# Morpheus_MEM.net
KiCad netlist of a schematic drawn in Altium Designer
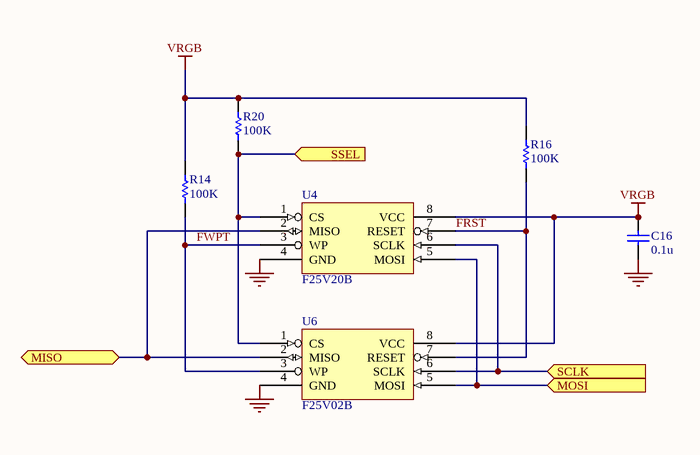
[diagram p0: Morpheus_MEM.SchDoc]

(export (version "E")
  (design (tool "Eeschema 10.0.6"))
  (components
    (comp (ref "C16")
      (value "0.1u")
      (footprint "CAP0402")
      (description "Chip capacitor")
      (fields (field (name "TOLERANCE") "10%") (field (name "VOLTAGE") "50V"))
      (libsource (lib "Hello") (part "C_0.1u_10_50_X7R_0402"))
    )
    (comp (ref "R14")
      (value "100K")
      (footprint "RES0402")
      (description "Chip Resistor")
      (fields (field (name "TOLERANCE") "5 %") (field (name "POWER") "0.1 W"))
      (libsource (lib "Hello") (part "R_100K_5_0.1_0402"))
    )
    (comp (ref "R16")
      (value "100K")
      (footprint "RES0402")
      (description "Chip Resistor")
      (fields (field (name "TOLERANCE") "5 %") (field (name "POWER") "0.1 W"))
      (libsource (lib "Hello") (part "R_100K_5_0.1_0402"))
    )
    (comp (ref "R20")
      (value "100K")
      (footprint "RES0402")
      (description "Chip Resistor")
      (fields (field (name "TOLERANCE") "5 %") (field (name "POWER") "0.1 W"))
      (libsource (lib "Hello") (part "R_100K_5_0.1_0402"))
    )
    (comp (ref "U4")
      (value "F25V20B")
      (footprint "DFN127P600x500x80-8N")
      (description "Cypress SPI FRAM 256Kx8")
      (libsource (lib "dykes") (part "FM25V20B"))
    )
    (comp (ref "U6")
      (value "F25V02B")
      (footprint "DFN95P5000x4500x80-8N")
      (description "Cypress SPI FRAM 32Kx8")
      (libsource (lib "dykes") (part "FM25V02B"))
    )
  )
  (nets
    (net (code "1") (name "/FRST") (class "Default")
      (node (ref "R16") (pin "1") (pinfunction "1_1") (pintype "passive"))
      (node (ref "U4") (pin "7") (pinfunction "RESET_7") (pintype "input"))
      (node (ref "U6") (pin "7") (pinfunction "RESET_7") (pintype "input"))
    )
    (net (code "2") (name "/FWPT") (class "Default")
      (node (ref "R14") (pin "1") (pinfunction "1_1") (pintype "passive"))
      (node (ref "U4") (pin "3") (pinfunction "WP_3") (pintype "passive"))
      (node (ref "U6") (pin "3") (pinfunction "WP_3") (pintype "passive"))
    )
    (net (code "3") (name "/MISO") (class "Default")
      (node (ref "U4") (pin "2") (pinfunction "MISO_2") (pintype "bidirectional"))
      (node (ref "U6") (pin "2") (pinfunction "MISO_2") (pintype "bidirectional"))
    )
    (net (code "4") (name "/MOSI") (class "Default")
      (node (ref "U4") (pin "5") (pinfunction "MOSI_5") (pintype "input"))
      (node (ref "U6") (pin "5") (pinfunction "MOSI_5") (pintype "input"))
    )
    (net (code "5") (name "/SCLK") (class "Default")
      (node (ref "U4") (pin "6") (pinfunction "SCLK_6") (pintype "input"))
      (node (ref "U6") (pin "6") (pinfunction "SCLK_6") (pintype "input"))
    )
    (net (code "6") (name "/SSEL") (class "Default")
      (node (ref "R20") (pin "1") (pinfunction "1_1") (pintype "passive"))
      (node (ref "U4") (pin "1") (pinfunction "CS_1") (pintype "input"))
      (node (ref "U6") (pin "1") (pinfunction "CS_1") (pintype "input"))
    )
    (net (code "7") (name "GND") (class "Default")
      (node (ref "C16") (pin "1") (pinfunction "1_1") (pintype "passive"))
      (node (ref "U4") (pin "4") (pinfunction "GND_4") (pintype "power_in"))
      (node (ref "U6") (pin "4") (pinfunction "GND_4") (pintype "power_in"))
    )
    (net (code "8") (name "VRGB") (class "Default")
      (node (ref "C16") (pin "2") (pinfunction "2_2") (pintype "passive"))
      (node (ref "R14") (pin "2") (pinfunction "2_2") (pintype "passive"))
      (node (ref "R16") (pin "2") (pinfunction "2_2") (pintype "passive"))
      (node (ref "R20") (pin "2") (pinfunction "2_2") (pintype "passive"))
      (node (ref "U4") (pin "8") (pinfunction "VCC_8") (pintype "power_in"))
      (node (ref "U6") (pin "8") (pinfunction "VCC_8") (pintype "power_in"))
    )
  )
)
